# 2.net
KiCad netlist of a schematic drawn in Altium Designer
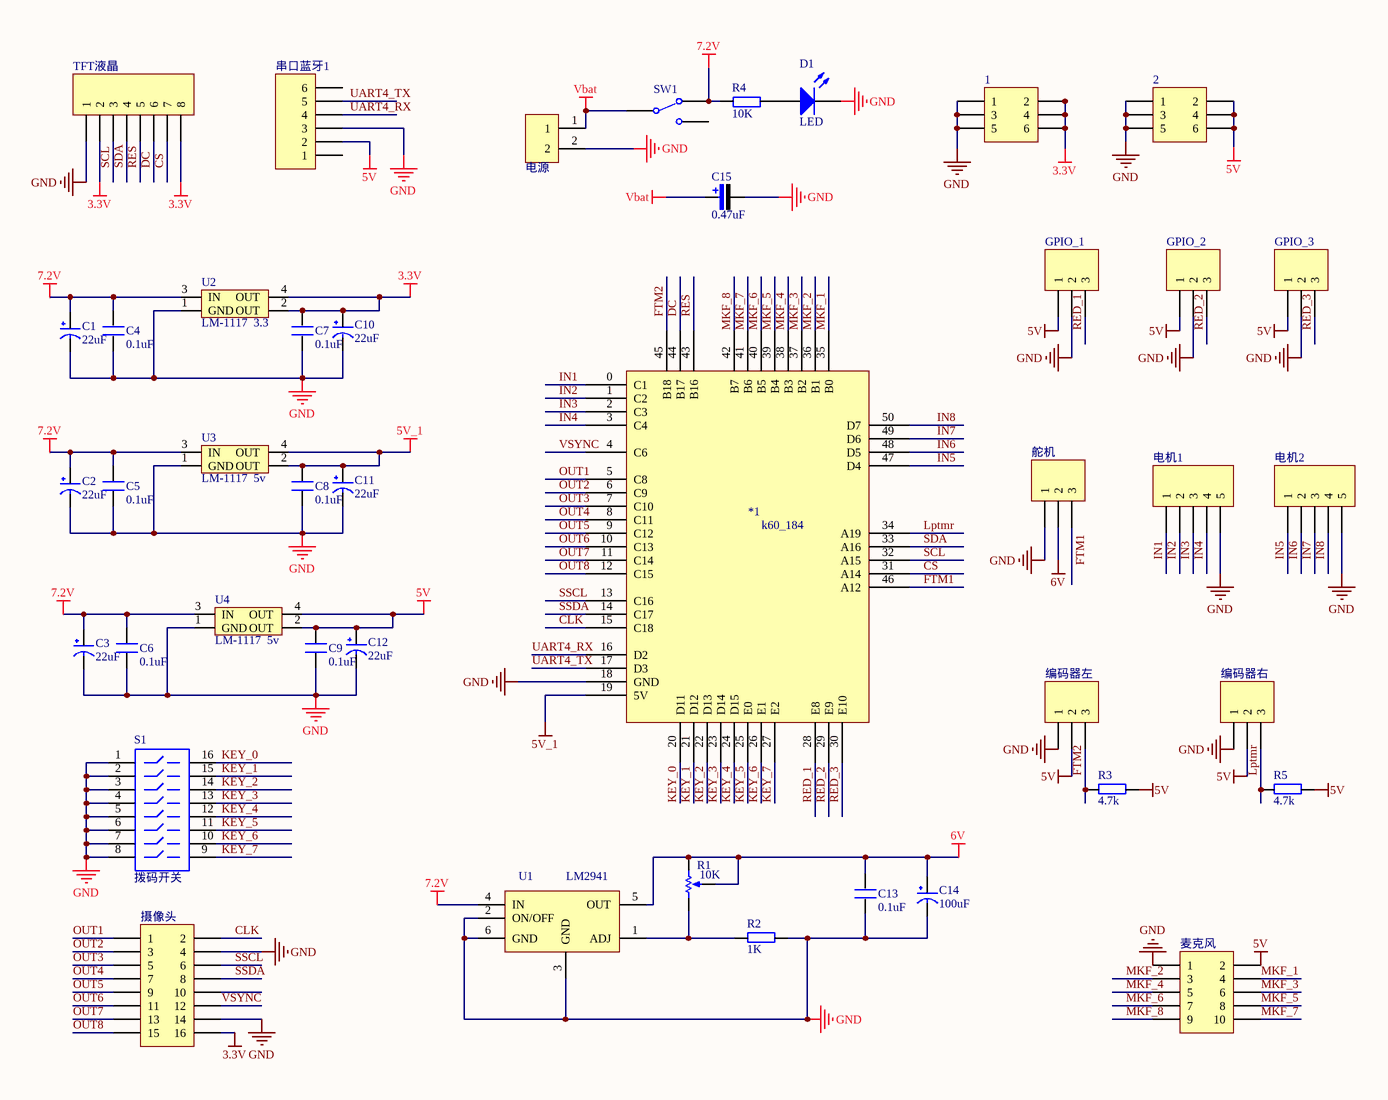
[diagram p0: 2.SchDoc]

(export (version "E")
  (design (tool "Eeschema 10.0.6"))
  (components
    (comp (ref "*1") (value "k60_184") (footprint "k60_184") (libsource (lib "bei") (part "k60_184")))
    (comp (ref "1")
      (value "Header 3X2")
      (footprint "HDR2X3")
      (description "Header, 3-Pin, Dual row")
      (fields (field (name "PUBLISHER") "Altium Limited"))
      (libsource (lib "Miscellaneous Connectors") (part "Header 3X2"))
    )
    (comp (ref "2")
      (value "Header 3X2")
      (footprint "HDR2X3")
      (description "Header, 3-Pin, Dual row")
      (fields (field (name "PUBLISHER") "Altium Limited"))
      (libsource (lib "Miscellaneous Connectors") (part "Header 3X2"))
    )
    (comp (ref "C1") (value "22uF") (footprint "0603") (libsource (lib "辅助元件库") (part "Cap+")))
    (comp (ref "C2") (value "22uF") (footprint "0603") (libsource (lib "辅助元件库") (part "Cap+")))
    (comp (ref "C3") (value "22uF") (footprint "0603") (libsource (lib "辅助元件库") (part "Cap+")))
    (comp (ref "C4") (value "0.1uF") (footprint "0603") (libsource (lib "辅助元件库") (part "Cap")))
    (comp (ref "C5") (value "0.1uF") (footprint "0603") (libsource (lib "辅助元件库") (part "Cap")))
    (comp (ref "C6") (value "0.1uF") (footprint "0603") (libsource (lib "辅助元件库") (part "Cap")))
    (comp (ref "C7") (value "0.1uF") (footprint "0603") (libsource (lib "辅助元件库") (part "Cap")))
    (comp (ref "C8") (value "0.1uF") (footprint "0603") (libsource (lib "辅助元件库") (part "Cap")))
    (comp (ref "C9") (value "0.1uF") (footprint "0603") (libsource (lib "辅助元件库") (part "Cap")))
    (comp (ref "C10") (value "22uF") (footprint "0603") (libsource (lib "辅助元件库") (part "Cap+")))
    (comp (ref "C11") (value "22uF") (footprint "0603") (libsource (lib "辅助元件库") (part "Cap+")))
    (comp (ref "C12") (value "22uF") (footprint "0603") (libsource (lib "辅助元件库") (part "Cap+")))
    (comp (ref "C13") (value "0.1uF") (footprint "0603") (libsource (lib "辅助元件库") (part "Cap")))
    (comp (ref "C14") (value "100uF") (footprint "1206钽") (libsource (lib "辅助元件库") (part "Cap+")))
    (comp (ref "C15")
      (value "0.47uF")
      (footprint "CAP-3528")
      (description "极性电解电容")
      (fields (field (name "Comment") "Cap Pol") (field (name "PUBLISHER") "Altium Limited"))
      (libsource (lib "Fszhang") (part "Cap Pol"))
    )
    (comp (ref "D1") (value "LED") (footprint "LED2") (libsource (lib "辅助元件库") (part "LED")))
    (comp (ref "GPIO_1")
      (value "GPIO")
      (footprint "HDR1X3")
      (description "Header, 3-Pin")
      (fields (field (name "PUBLISHER") "Altium Limited"))
      (libsource (lib "Miscellaneous Connectors") (part "Header 3"))
    )
    (comp (ref "GPIO_2")
      (value "GPIO")
      (footprint "HDR1X3")
      (description "Header, 3-Pin")
      (fields (field (name "PUBLISHER") "Altium Limited"))
      (libsource (lib "Miscellaneous Connectors") (part "Header 3"))
    )
    (comp (ref "GPIO_3")
      (value "GPIO")
      (footprint "HDR1X3")
      (description "Header, 3-Pin")
      (fields (field (name "PUBLISHER") "Altium Limited"))
      (libsource (lib "Miscellaneous Connectors") (part "Header 3"))
    )
    (comp (ref "R1")
      (value "10K")
      (footprint "VR_B1")
      (description "精密可调电阻")
      (fields (field (name "Comment") "RPot") (field (name "PUBLISHER") "Altium Limited"))
      (libsource (lib "Fszhang") (part "RPot"))
    )
    (comp (ref "R2") (value "1K") (footprint "0603") (libsource (lib "辅助元件库") (part "R")))
    (comp (ref "R3") (value "4.7k") (footprint "0603") (libsource (lib "辅助元件库") (part "R")))
    (comp (ref "R4") (value "10K") (footprint "0603") (libsource (lib "辅助元件库") (part "R")))
    (comp (ref "R5") (value "4.7k") (footprint "0603") (libsource (lib "辅助元件库") (part "R")))
    (comp (ref "S1")
      (value "拨码开关")
      (footprint "DIP16-KEY")
      (description "8位直插拨码开关")
      (fields (field (name "PUBLISHER") "Altium Limited"))
      (libsource (lib "Fszhang") (part "SW-DIP8"))
    )
    (comp (ref "SW1") (value "SW-纽子") (footprint "SW-纽子") (libsource (lib "辅助元件库") (part "SW-纽子")))
    (comp (ref "TFT液晶")
      (value "TFT液晶")
      (footprint "HDR1X8")
      (description "Header, 8-Pin")
      (fields (field (name "PUBLISHER") "Altium Limited"))
      (libsource (lib "Miscellaneous Connectors") (part "Header 8"))
    )
    (comp (ref "U1") (value "LM2941") (footprint "LM2941") (libsource (lib "辅助元件库") (part "LM2941")))
    (comp (ref "U2")
      (value "LM-1117  3.3")
      (footprint "SOT220P700X180-4N")
      (libsource (lib "辅助元件库") (part "AMS-1117"))
    )
    (comp (ref "U3")
      (value "LM-1117  5v")
      (footprint "SOT220P700X180-4N")
      (libsource (lib "辅助元件库") (part "AMS-1117"))
    )
    (comp (ref "U4")
      (value "LM-1117  5v")
      (footprint "SOT220P700X180-4N")
      (libsource (lib "辅助元件库") (part "AMS-1117"))
    )
    (comp (ref "串口蓝牙1")
      (value "Header 6")
      (footprint "HDR1X6")
      (description "Header, 6-Pin")
      (fields (field (name "PUBLISHER") "Altium Limited"))
      (libsource (lib "Miscellaneous Connectors") (part "Header 6"))
    )
    (comp (ref "摄像头")
      (value "Header 8X2")
      (footprint "HDR2X8")
      (description "Header, 8-Pin, Dual row")
      (fields (field (name "PUBLISHER") "Altium Limited"))
      (libsource (lib "Miscellaneous Connectors") (part "Header 8X2"))
    )
    (comp (ref "电机1")
      (value "电机")
      (footprint "HDR1X5")
      (description "Header, 5-Pin")
      (fields (field (name "PUBLISHER") "Altium Limited"))
      (libsource (lib "Miscellaneous Connectors") (part "Header 5"))
    )
    (comp (ref "电机2")
      (value "电机")
      (footprint "HDR1X5")
      (description "Header, 5-Pin")
      (fields (field (name "PUBLISHER") "Altium Limited"))
      (libsource (lib "Miscellaneous Connectors") (part "Header 5"))
    )
    (comp (ref "电源") (value "电机") (footprint "接线端子") (libsource (lib "辅助元件库") (part "接线端子")))
    (comp (ref "编码器右")
      (value "Header 3")
      (footprint "HDR1X3")
      (description "Header, 3-Pin")
      (fields (field (name "PUBLISHER") "Altium Limited"))
      (libsource (lib "Miscellaneous Connectors") (part "Header 3"))
    )
    (comp (ref "编码器左")
      (value "Header 3")
      (footprint "HDR1X3")
      (description "Header, 3-Pin")
      (fields (field (name "PUBLISHER") "Altium Limited"))
      (libsource (lib "Miscellaneous Connectors") (part "Header 3"))
    )
    (comp (ref "舵机")
      (value "Header 3")
      (footprint "HDR1X3")
      (description "Header, 3-Pin")
      (fields (field (name "PUBLISHER") "Altium Limited"))
      (libsource (lib "Miscellaneous Connectors") (part "Header 3"))
    )
    (comp (ref "麦克风")
      (value "Header 5X2")
      (footprint "HDR2X5")
      (description "Header, 5-Pin, Dual row")
      (fields (field (name "PUBLISHER") "Altium Limited"))
      (libsource (lib "Miscellaneous Connectors") (part "Header 5X2"))
    )
  )
  (nets
    (net (code "1") (name "/CLK") (class "Default")
      (node (ref "*1") (pin "15") (pinfunction "C18_15") (pintype "passive"))
      (node (ref "摄像头") (pin "2") (pinfunction "2_2") (pintype "passive"))
    )
    (net (code "2") (name "/CS") (class "Default")
      (node (ref "*1") (pin "31") (pinfunction "A14_31") (pintype "passive"))
      (node (ref "TFT液晶") (pin "7") (pinfunction "7_7") (pintype "passive"))
    )
    (net (code "3") (name "/DC") (class "Default")
      (node (ref "*1") (pin "44") (pinfunction "B17_44") (pintype "passive"))
      (node (ref "TFT液晶") (pin "6") (pinfunction "6_6") (pintype "passive"))
    )
    (net (code "4") (name "/FTM1") (class "Default")
      (node (ref "*1") (pin "46") (pinfunction "A12_46") (pintype "passive"))
      (node (ref "舵机") (pin "3") (pinfunction "3_3") (pintype "passive"))
    )
    (net (code "5") (name "/FTM2") (class "Default")
      (node (ref "*1") (pin "45") (pinfunction "B18_45") (pintype "passive"))
      (node (ref "R3") (pin "2") (pintype "passive"))
      (node (ref "编码器左") (pin "3") (pinfunction "3_3") (pintype "passive"))
    )
    (net (code "6") (name "/IN1") (class "Default")
      (node (ref "*1") (pin "0") (pinfunction "C1_0") (pintype "passive"))
      (node (ref "电机1") (pin "1") (pinfunction "1_1") (pintype "passive"))
    )
    (net (code "7") (name "/IN2") (class "Default")
      (node (ref "*1") (pin "1") (pinfunction "C2_1") (pintype "passive"))
      (node (ref "电机1") (pin "2") (pinfunction "2_2") (pintype "passive"))
    )
    (net (code "8") (name "/IN3") (class "Default")
      (node (ref "*1") (pin "2") (pinfunction "C3_2") (pintype "passive"))
      (node (ref "电机1") (pin "3") (pinfunction "3_3") (pintype "passive"))
    )
    (net (code "9") (name "/IN4") (class "Default")
      (node (ref "*1") (pin "3") (pinfunction "C4_3") (pintype "passive"))
      (node (ref "电机1") (pin "4") (pinfunction "4_4") (pintype "passive"))
    )
    (net (code "10") (name "/IN5") (class "Default")
      (node (ref "*1") (pin "47") (pinfunction "D4_47") (pintype "passive"))
      (node (ref "电机2") (pin "1") (pinfunction "1_1") (pintype "passive"))
    )
    (net (code "11") (name "/IN6") (class "Default")
      (node (ref "*1") (pin "48") (pinfunction "D5_48") (pintype "passive"))
      (node (ref "电机2") (pin "2") (pinfunction "2_2") (pintype "passive"))
    )
    (net (code "12") (name "/IN7") (class "Default")
      (node (ref "*1") (pin "49") (pinfunction "D6_49") (pintype "passive"))
      (node (ref "电机2") (pin "3") (pinfunction "3_3") (pintype "passive"))
    )
    (net (code "13") (name "/IN8") (class "Default")
      (node (ref "*1") (pin "50") (pinfunction "D7_50") (pintype "passive"))
      (node (ref "电机2") (pin "4") (pinfunction "4_4") (pintype "passive"))
    )
    (net (code "14") (name "/KEY_0") (class "Default")
      (node (ref "*1") (pin "20") (pinfunction "D11_20") (pintype "passive"))
      (node (ref "S1") (pin "16") (pinfunction "16_16") (pintype "passive"))
    )
    (net (code "15") (name "/KEY_1") (class "Default")
      (node (ref "*1") (pin "21") (pinfunction "D12_21") (pintype "passive"))
      (node (ref "S1") (pin "15") (pinfunction "15_15") (pintype "passive"))
    )
    (net (code "16") (name "/KEY_2") (class "Default")
      (node (ref "*1") (pin "22") (pinfunction "D13_22") (pintype "passive"))
      (node (ref "S1") (pin "14") (pinfunction "14_14") (pintype "passive"))
    )
    (net (code "17") (name "/KEY_3") (class "Default")
      (node (ref "*1") (pin "23") (pinfunction "D14_23") (pintype "passive"))
      (node (ref "S1") (pin "13") (pinfunction "13_13") (pintype "passive"))
    )
    (net (code "18") (name "/KEY_4") (class "Default")
      (node (ref "*1") (pin "24") (pinfunction "D15_24") (pintype "passive"))
      (node (ref "S1") (pin "12") (pinfunction "12_12") (pintype "passive"))
    )
    (net (code "19") (name "/KEY_5") (class "Default")
      (node (ref "*1") (pin "25") (pinfunction "E0_25") (pintype "passive"))
      (node (ref "S1") (pin "11") (pinfunction "11_11") (pintype "passive"))
    )
    (net (code "20") (name "/KEY_6") (class "Default")
      (node (ref "*1") (pin "26") (pinfunction "E1_26") (pintype "passive"))
      (node (ref "S1") (pin "10") (pinfunction "10_10") (pintype "passive"))
    )
    (net (code "21") (name "/KEY_7") (class "Default")
      (node (ref "*1") (pin "27") (pinfunction "E2_27") (pintype "passive"))
      (node (ref "S1") (pin "9") (pinfunction "9_9") (pintype "passive"))
    )
    (net (code "22") (name "/Lptmr") (class "Default")
      (node (ref "*1") (pin "34") (pinfunction "A19_34") (pintype "passive"))
      (node (ref "R5") (pin "2") (pintype "passive"))
      (node (ref "编码器右") (pin "3") (pinfunction "3_3") (pintype "passive"))
    )
    (net (code "23") (name "/MKF_1") (class "Default")
      (node (ref "*1") (pin "35") (pinfunction "B0_35") (pintype "passive"))
      (node (ref "麦克风") (pin "4") (pinfunction "4_4") (pintype "passive"))
    )
    (net (code "24") (name "/MKF_2") (class "Default")
      (node (ref "*1") (pin "36") (pinfunction "B1_36") (pintype "passive"))
      (node (ref "麦克风") (pin "3") (pinfunction "3_3") (pintype "passive"))
    )
    (net (code "25") (name "/MKF_3") (class "Default")
      (node (ref "*1") (pin "37") (pinfunction "B2_37") (pintype "passive"))
      (node (ref "麦克风") (pin "6") (pinfunction "6_6") (pintype "passive"))
    )
    (net (code "26") (name "/MKF_4") (class "Default")
      (node (ref "*1") (pin "38") (pinfunction "B3_38") (pintype "passive"))
      (node (ref "麦克风") (pin "5") (pinfunction "5_5") (pintype "passive"))
    )
    (net (code "27") (name "/MKF_5") (class "Default")
      (node (ref "*1") (pin "39") (pinfunction "B4_39") (pintype "passive"))
      (node (ref "麦克风") (pin "8") (pinfunction "8_8") (pintype "passive"))
    )
    (net (code "28") (name "/MKF_6") (class "Default")
      (node (ref "*1") (pin "40") (pinfunction "B5_40") (pintype "passive"))
      (node (ref "麦克风") (pin "7") (pinfunction "7_7") (pintype "passive"))
    )
    (net (code "29") (name "/MKF_7") (class "Default")
      (node (ref "*1") (pin "41") (pinfunction "B6_41") (pintype "passive"))
      (node (ref "麦克风") (pin "10") (pinfunction "10_10") (pintype "passive"))
    )
    (net (code "30") (name "/MKF_8") (class "Default")
      (node (ref "*1") (pin "42") (pinfunction "B7_42") (pintype "passive"))
      (node (ref "麦克风") (pin "9") (pinfunction "9_9") (pintype "passive"))
    )
    (net (code "31") (name "/OUT1") (class "Default")
      (node (ref "*1") (pin "5") (pinfunction "C8_5") (pintype "passive"))
      (node (ref "摄像头") (pin "1") (pinfunction "1_1") (pintype "passive"))
    )
    (net (code "32") (name "/OUT2") (class "Default")
      (node (ref "*1") (pin "6") (pinfunction "C9_6") (pintype "passive"))
      (node (ref "摄像头") (pin "3") (pinfunction "3_3") (pintype "passive"))
    )
    (net (code "33") (name "/OUT3") (class "Default")
      (node (ref "*1") (pin "7") (pinfunction "C10_7") (pintype "passive"))
      (node (ref "摄像头") (pin "5") (pinfunction "5_5") (pintype "passive"))
    )
    (net (code "34") (name "/OUT4") (class "Default")
      (node (ref "*1") (pin "8") (pinfunction "C11_8") (pintype "passive"))
      (node (ref "摄像头") (pin "7") (pinfunction "7_7") (pintype "passive"))
    )
    (net (code "35") (name "/OUT5") (class "Default")
      (node (ref "*1") (pin "9") (pinfunction "C12_9") (pintype "passive"))
      (node (ref "摄像头") (pin "9") (pinfunction "9_9") (pintype "passive"))
    )
    (net (code "36") (name "/OUT6") (class "Default")
      (node (ref "*1") (pin "10") (pinfunction "C13_10") (pintype "passive"))
      (node (ref "摄像头") (pin "11") (pinfunction "11_11") (pintype "passive"))
    )
    (net (code "37") (name "/OUT7") (class "Default")
      (node (ref "*1") (pin "11") (pinfunction "C14_11") (pintype "passive"))
      (node (ref "摄像头") (pin "13") (pinfunction "13_13") (pintype "passive"))
    )
    (net (code "38") (name "/OUT8") (class "Default")
      (node (ref "*1") (pin "12") (pinfunction "C15_12") (pintype "passive"))
      (node (ref "摄像头") (pin "15") (pinfunction "15_15") (pintype "passive"))
    )
    (net (code "39") (name "/RED_1") (class "Default")
      (node (ref "*1") (pin "28") (pinfunction "E8_28") (pintype "passive"))
      (node (ref "GPIO_1") (pin "3") (pinfunction "3_3") (pintype "passive"))
    )
    (net (code "40") (name "/RED_2") (class "Default")
      (node (ref "*1") (pin "29") (pinfunction "E9_29") (pintype "passive"))
      (node (ref "GPIO_2") (pin "3") (pinfunction "3_3") (pintype "passive"))
    )
    (net (code "41") (name "/RED_3") (class "Default")
      (node (ref "*1") (pin "30") (pinfunction "E10_30") (pintype "passive"))
      (node (ref "GPIO_3") (pin "3") (pinfunction "3_3") (pintype "passive"))
    )
    (net (code "42") (name "/RES") (class "Default")
      (node (ref "*1") (pin "43") (pinfunction "B16_43") (pintype "passive"))
      (node (ref "TFT液晶") (pin "5") (pinfunction "5_5") (pintype "passive"))
    )
    (net (code "43") (name "/SCL") (class "Default")
      (node (ref "*1") (pin "32") (pinfunction "A15_32") (pintype "passive"))
      (node (ref "TFT液晶") (pin "3") (pinfunction "3_3") (pintype "passive"))
    )
    (net (code "44") (name "/SDA") (class "Default")
      (node (ref "*1") (pin "33") (pinfunction "A16_33") (pintype "passive"))
      (node (ref "TFT液晶") (pin "4") (pinfunction "4_4") (pintype "passive"))
    )
    (net (code "45") (name "/SSCL") (class "Default")
      (node (ref "*1") (pin "13") (pinfunction "C16_13") (pintype "passive"))
      (node (ref "摄像头") (pin "6") (pinfunction "6_6") (pintype "passive"))
    )
    (net (code "46") (name "/SSDA") (class "Default")
      (node (ref "*1") (pin "14") (pinfunction "C17_14") (pintype "passive"))
      (node (ref "摄像头") (pin "8") (pinfunction "8_8") (pintype "passive"))
    )
    (net (code "47") (name "/UART4_RX") (class "Default")
      (node (ref "*1") (pin "16") (pinfunction "D2_16") (pintype "passive"))
      (node (ref "串口蓝牙1") (pin "4") (pinfunction "4_4") (pintype "passive"))
    )
    (net (code "48") (name "/UART4_TX") (class "Default")
      (node (ref "*1") (pin "17") (pinfunction "D3_17") (pintype "passive"))
      (node (ref "串口蓝牙1") (pin "5") (pinfunction "5_5") (pintype "passive"))
    )
    (net (code "49") (name "/VSYNC") (class "Default")
      (node (ref "*1") (pin "4") (pinfunction "C6_4") (pintype "passive"))
      (node (ref "摄像头") (pin "12") (pinfunction "12_12") (pintype "passive"))
    )
    (net (code "50") (name "3.3V") (class "Default")
      (node (ref "1") (pin "2") (pinfunction "2_2") (pintype "passive"))
      (node (ref "1") (pin "4") (pinfunction "4_4") (pintype "passive"))
      (node (ref "1") (pin "6") (pinfunction "6_6") (pintype "passive"))
      (node (ref "C10") (pin "1") (pinfunction "VCC_1") (pintype "passive"))
      (node (ref "C7") (pin "2") (pintype "passive"))
      (node (ref "TFT液晶") (pin "2") (pinfunction "2_2") (pintype "passive"))
      (node (ref "TFT液晶") (pin "8") (pinfunction "8_8") (pintype "passive"))
      (node (ref "U2") (pin "2") (pinfunction "OUT_2") (pintype "passive"))
      (node (ref "U2") (pin "4") (pinfunction "OUT_4") (pintype "passive"))
      (node (ref "摄像头") (pin "16") (pinfunction "16_16") (pintype "passive"))
    )
    (net (code "51") (name "5V") (class "Default")
      (node (ref "2") (pin "2") (pinfunction "2_2") (pintype "passive"))
      (node (ref "2") (pin "4") (pinfunction "4_4") (pintype "passive"))
      (node (ref "2") (pin "6") (pinfunction "6_6") (pintype "passive"))
      (node (ref "C12") (pin "1") (pinfunction "VCC_1") (pintype "passive"))
      (node (ref "C9") (pin "2") (pintype "passive"))
      (node (ref "GPIO_1") (pin "1") (pinfunction "1_1") (pintype "passive"))
      (node (ref "GPIO_2") (pin "1") (pinfunction "1_1") (pintype "passive"))
      (node (ref "GPIO_3") (pin "1") (pinfunction "1_1") (pintype "passive"))
      (node (ref "R3") (pin "1") (pintype "passive"))
      (node (ref "R5") (pin "1") (pintype "passive"))
      (node (ref "U4") (pin "2") (pinfunction "OUT_2") (pintype "passive"))
      (node (ref "U4") (pin "4") (pinfunction "OUT_4") (pintype "passive"))
      (node (ref "串口蓝牙1") (pin "2") (pinfunction "2_2") (pintype "passive"))
      (node (ref "编码器右") (pin "2") (pinfunction "2_2") (pintype "passive"))
      (node (ref "编码器左") (pin "2") (pinfunction "2_2") (pintype "passive"))
      (node (ref "麦克风") (pin "2") (pinfunction "2_2") (pintype "passive"))
    )
    (net (code "52") (name "5V_1") (class "Default")
      (node (ref "*1") (pin "19") (pinfunction "5V_19") (pintype "passive"))
      (node (ref "C11") (pin "1") (pinfunction "VCC_1") (pintype "passive"))
      (node (ref "C8") (pin "2") (pintype "passive"))
      (node (ref "U3") (pin "2") (pinfunction "OUT_2") (pintype "passive"))
      (node (ref "U3") (pin "4") (pinfunction "OUT_4") (pintype "passive"))
    )
    (net (code "53") (name "6V") (class "Default")
      (node (ref "C13") (pin "2") (pintype "passive"))
      (node (ref "C14") (pin "1") (pinfunction "VCC_1") (pintype "passive"))
      (node (ref "R1") (pin "2") (pinfunction "TAP_2") (pintype "passive"))
      (node (ref "R1") (pin "3") (pinfunction "BOT_3") (pintype "passive"))
      (node (ref "U1") (pin "5") (pinfunction "OUT_5") (pintype "open_collector"))
      (node (ref "舵机") (pin "2") (pinfunction "2_2") (pintype "passive"))
    )
    (net (code "54") (name "7.2V") (class "Default")
      (node (ref "C1") (pin "1") (pinfunction "VCC_1") (pintype "passive"))
      (node (ref "C2") (pin "1") (pinfunction "VCC_1") (pintype "passive"))
      (node (ref "C3") (pin "1") (pinfunction "VCC_1") (pintype "passive"))
      (node (ref "C4") (pin "2") (pintype "passive"))
      (node (ref "C5") (pin "2") (pintype "passive"))
      (node (ref "C6") (pin "2") (pintype "passive"))
      (node (ref "R4") (pin "1") (pintype "passive"))
      (node (ref "SW1") (pin "1") (pinfunction "NO_1") (pintype "passive"))
      (node (ref "U1") (pin "4") (pinfunction "IN_4") (pintype "open_collector"))
      (node (ref "U2") (pin "3") (pinfunction "IN_3") (pintype "passive"))
      (node (ref "U3") (pin "3") (pinfunction "IN_3") (pintype "passive"))
      (node (ref "U4") (pin "3") (pinfunction "IN_3") (pintype "passive"))
    )
    (net (code "55") (name "GND") (class "Default")
      (node (ref "*1") (pin "18") (pinfunction "GND_18") (pintype "passive"))
      (node (ref "1") (pin "1") (pinfunction "1_1") (pintype "passive"))
      (node (ref "1") (pin "3") (pinfunction "3_3") (pintype "passive"))
      (node (ref "1") (pin "5") (pinfunction "5_5") (pintype "passive"))
      (node (ref "2") (pin "1") (pinfunction "1_1") (pintype "passive"))
      (node (ref "2") (pin "3") (pinfunction "3_3") (pintype "passive"))
      (node (ref "2") (pin "5") (pinfunction "5_5") (pintype "passive"))
      (node (ref "C1") (pin "2") (pinfunction "GND_2") (pintype "passive"))
      (node (ref "C10") (pin "2") (pinfunction "GND_2") (pintype "passive"))
      (node (ref "C11") (pin "2") (pinfunction "GND_2") (pintype "passive"))
      (node (ref "C12") (pin "2") (pinfunction "GND_2") (pintype "passive"))
      (node (ref "C13") (pin "1") (pintype "passive"))
      (node (ref "C14") (pin "2") (pinfunction "GND_2") (pintype "passive"))
      (node (ref "C15") (pin "2") (pinfunction "2_2") (pintype "passive"))
      (node (ref "C2") (pin "2") (pinfunction "GND_2") (pintype "passive"))
      (node (ref "C3") (pin "2") (pinfunction "GND_2") (pintype "passive"))
      (node (ref "C4") (pin "1") (pintype "passive"))
      (node (ref "C5") (pin "1") (pintype "passive"))
      (node (ref "C6") (pin "1") (pintype "passive"))
      (node (ref "C7") (pin "1") (pintype "passive"))
      (node (ref "C8") (pin "1") (pintype "passive"))
      (node (ref "C9") (pin "1") (pintype "passive"))
      (node (ref "D1") (pin "2") (pinfunction "K_2") (pintype "passive"))
      (node (ref "GPIO_1") (pin "2") (pinfunction "2_2") (pintype "passive"))
      (node (ref "GPIO_2") (pin "2") (pinfunction "2_2") (pintype "passive"))
      (node (ref "GPIO_3") (pin "2") (pinfunction "2_2") (pintype "passive"))
      (node (ref "R2") (pin "1") (pintype "passive"))
      (node (ref "S1") (pin "1") (pinfunction "1_1") (pintype "passive"))
      (node (ref "S1") (pin "2") (pinfunction "2_2") (pintype "passive"))
      (node (ref "S1") (pin "3") (pinfunction "3_3") (pintype "passive"))
      (node (ref "S1") (pin "4") (pinfunction "4_4") (pintype "passive"))
      (node (ref "S1") (pin "5") (pinfunction "5_5") (pintype "passive"))
      (node (ref "S1") (pin "6") (pinfunction "6_6") (pintype "passive"))
      (node (ref "S1") (pin "7") (pinfunction "7_7") (pintype "passive"))
      (node (ref "S1") (pin "8") (pinfunction "8_8") (pintype "passive"))
      (node (ref "TFT液晶") (pin "1") (pinfunction "1_1") (pintype "passive"))
      (node (ref "U1") (pin "2") (pinfunction "ON/OFF_2") (pintype "open_collector"))
      (node (ref "U1") (pin "3") (pinfunction "GND_3") (pintype "open_collector"))
      (node (ref "U1") (pin "6") (pinfunction "GND_6") (pintype "open_collector"))
      (node (ref "U2") (pin "1") (pinfunction "GND_1") (pintype "passive"))
      (node (ref "U3") (pin "1") (pinfunction "GND_1") (pintype "passive"))
      (node (ref "U4") (pin "1") (pinfunction "GND_1") (pintype "passive"))
      (node (ref "串口蓝牙1") (pin "3") (pinfunction "3_3") (pintype "passive"))
      (node (ref "摄像头") (pin "14") (pinfunction "14_14") (pintype "passive"))
      (node (ref "摄像头") (pin "4") (pinfunction "4_4") (pintype "passive"))
      (node (ref "电机1") (pin "5") (pinfunction "5_5") (pintype "passive"))
      (node (ref "电机2") (pin "5") (pinfunction "5_5") (pintype "passive"))
      (node (ref "电源") (pin "2") (pinfunction "2_2") (pintype "open_collector"))
      (node (ref "编码器右") (pin "1") (pinfunction "1_1") (pintype "passive"))
      (node (ref "编码器左") (pin "1") (pinfunction "1_1") (pintype "passive"))
      (node (ref "舵机") (pin "1") (pinfunction "1_1") (pintype "passive"))
      (node (ref "麦克风") (pin "1") (pinfunction "1_1") (pintype "passive"))
    )
    (net (code "56") (name "Net-(D1-A)") (class "Default")
      (node (ref "D1") (pin "1") (pinfunction "A_1") (pintype "passive"))
      (node (ref "R4") (pin "2") (pintype "passive"))
    )
    (net (code "57") (name "Net-(R1-TOP)") (class "Default")
      (node (ref "R1") (pin "1") (pinfunction "TOP_1") (pintype "passive"))
      (node (ref "R2") (pin "2") (pintype "passive"))
      (node (ref "U1") (pin "1") (pinfunction "ADJ_1") (pintype "open_collector"))
    )
    (net (code "58") (name "Vbat") (class "Default")
      (node (ref "C15") (pin "1") (pinfunction "1_1") (pintype "passive"))
      (node (ref "SW1") (pin "2") (pinfunction "COMMON_2") (pintype "passive"))
      (node (ref "电源") (pin "1") (pinfunction "1_1") (pintype "open_collector"))
    )
    (net (code "59") (name "unconnected-(SW1-OFF-Pad3)") (class "Default")
      (node (ref "SW1") (pin "3") (pinfunction "OFF_3") (pintype "passive"))
    )
    (net (code "60") (name "unconnected-(串口蓝牙1-Pad1)") (class "Default")
      (node (ref "串口蓝牙1") (pin "1") (pinfunction "1_1") (pintype "passive"))
    )
    (net (code "61") (name "unconnected-(串口蓝牙1-Pad6)") (class "Default")
      (node (ref "串口蓝牙1") (pin "6") (pinfunction "6_6") (pintype "passive"))
    )
    (net (code "62") (name "unconnected-(摄像头-Pad10)") (class "Default")
      (node (ref "摄像头") (pin "10") (pinfunction "10_10") (pintype "passive"))
    )
  )
)
